# Schematic_nathanlin.net
KiCad netlist of a schematic drawn in Altium Designer
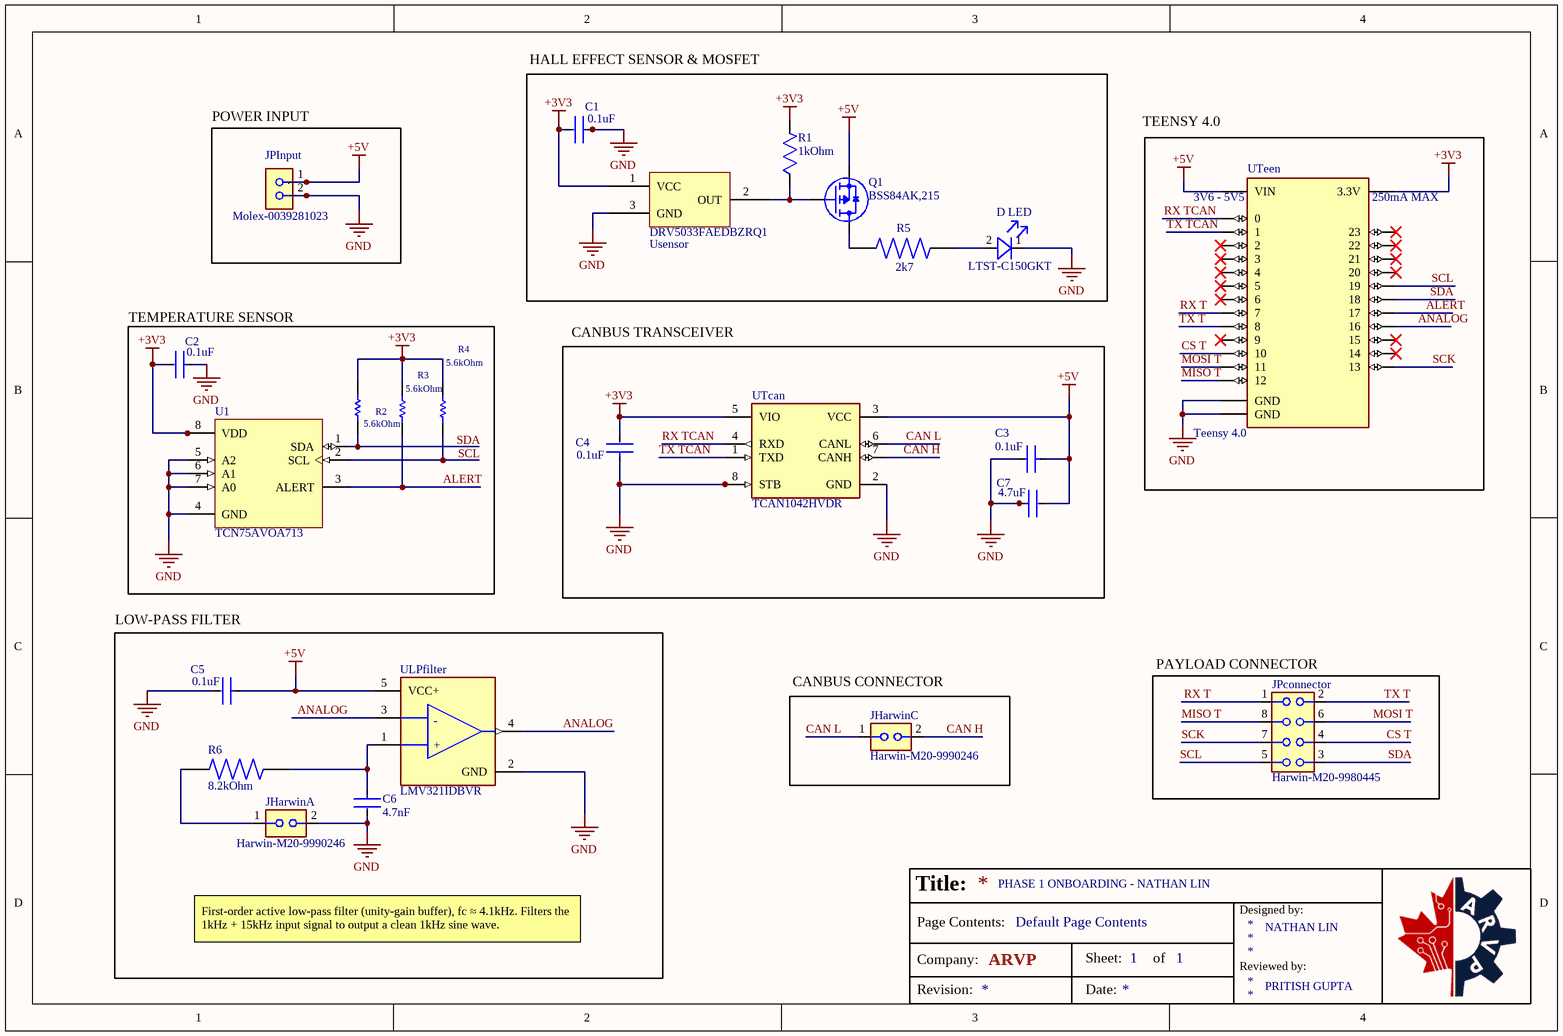
[diagram p0: Schematic_nathanlin.SchDoc]

(export (version "E")
  (design (tool "Eeschema 10.0.6"))
  (components
    (comp (ref "C1")
      (value "0.1uF")
      (footprint "CAP_0603")
      (description "CAP CER 0.1UF 50V X7R 0603")
      (fields (field (name "JLCPCB PART NO.") "C14663"))
      (libsource (lib "Autonomous Robotic Vehicle Project (ARVP)- University of Alberta") (part "CAP_UNPOLARIZED"))
    )
    (comp (ref "C2")
      (value "0.1uF")
      (footprint "CAP_0603")
      (description "CAP CER 0.1UF 50V X7R 0603")
      (fields (field (name "JLCPCB PART NO.") "C14663"))
      (libsource (lib "Autonomous Robotic Vehicle Project (ARVP)- University of Alberta") (part "CAP_UNPOLARIZED"))
    )
    (comp (ref "C3")
      (value "0.1uF")
      (footprint "CAP_0603")
      (description "CAP CER 0.1UF 50V X7R 0603")
      (fields (field (name "JLCPCB PART NO.") "C14663"))
      (libsource (lib "Autonomous Robotic Vehicle Project (ARVP)- University of Alberta") (part "CAP_UNPOLARIZED"))
    )
    (comp (ref "C4")
      (value "0.1uF")
      (footprint "CAP_0603")
      (description "CAP CER 0.1UF 50V X7R 0603")
      (fields (field (name "JLCPCB PART NO.") "C14663"))
      (libsource (lib "Autonomous Robotic Vehicle Project (ARVP)- University of Alberta") (part "CAP_UNPOLARIZED"))
    )
    (comp (ref "C5")
      (value "0.1uF")
      (footprint "CAP_0603")
      (description "CAP CER 0.1UF 50V X7R 0603")
      (fields (field (name "JLCPCB PART NO.") "C14663"))
      (libsource (lib "Autonomous Robotic Vehicle Project (ARVP)- University of Alberta") (part "CAP_UNPOLARIZED"))
    )
    (comp (ref "C6")
      (value "4.7nF")
      (footprint "CAP_0603")
      (description "4700 pF ±10% 50V Ceramic Capacitor X7R 0603 (1608 Metric)")
      (fields (field (name "JLCPCB PART NO.") "C1621"))
      (libsource (lib "Autonomous Robotic Vehicle Project (ARVP)- University of Alberta") (part "CAP_UNPOLARIZED"))
    )
    (comp (ref "C7")
      (value "4.7uF")
      (footprint "CAP_0603")
      (description "CAP CER 4.7UF 16V X5R 0603")
      (fields (field (name "JLCPCB PART NO.") "C19666"))
      (libsource (lib "Autonomous Robotic Vehicle Project (ARVP)- University of Alberta") (part "CAP_UNPOLARIZED"))
    )
    (comp (ref "D LED")
      (value "LTST-C150GKT")
      (footprint "LED_1206")
      (description "LED GREEN CLEAR 1206 SMD")
      (fields (field (name "JLCPCB PART NO.") "C125084"))
      (libsource (lib "Autonomous Robotic Vehicle Project (ARVP)- University of Alberta") (part "LED"))
    )
    (comp (ref "JHarwinA")
      (value "Harwin-M20-9990246")
      (footprint "HARWIN_M20-9990246")
      (description "Connector Header Through Hole 2 position 0.100\" (2.54mm)")
      (fields (field (name "JLCPCB PART NO.") "C3332353"))
      (libsource (lib "Autonomous Robotic Vehicle Project (ARVP)- University of Alberta") (part "M20-9990246"))
    )
    (comp (ref "JHarwinC")
      (value "Harwin-M20-9990246")
      (footprint "HARWIN_M20-9990246")
      (description "Connector Header Through Hole 2 position 0.100\" (2.54mm)")
      (fields (field (name "JLCPCB PART NO.") "C3332353"))
      (libsource (lib "Autonomous Robotic Vehicle Project (ARVP)- University of Alberta") (part "M20-9990246"))
    )
    (comp (ref "JPconnector")
      (value "Harwin-M20-9980445")
      (footprint "HARWIN_M20-9980445")
      (description "Connector Header Through Hole 8 position 0.100\" (2.54mm)")
      (fields (field (name "JLCPCB PART NO.") "C6897587") (field (name "MF") "Harwin Inc."))
      (libsource (lib "Autonomous Robotic Vehicle Project (ARVP)- University of Alberta") (part "M20-9980445"))
    )
    (comp (ref "JPInput")
      (value "Molex-0039281023")
      (footprint "0039281023")
      (description "Connector Header Through Hole 2 position")
      (fields (field (name "JLCPCB PART NO.") "C9900017326"))
      (libsource (lib "Autonomous Robotic Vehicle Project (ARVP)- University of Alberta") (part "0039281023"))
    )
    (comp (ref "Q1")
      (value "BSS84AK,215")
      (footprint "Nexperia_SOT-23-3")
      (description "P-Channel 50 V 180mA (Ta) 350mW (Ta), 1.14W (Tc) Surface Mount TO-236AB")
      (fields (field (name "JLCPCB PART NO.") "C127273"))
      (libsource (lib "Autonomous Robotic Vehicle Project (ARVP)- University of Alberta") (part "BSS84AK,215"))
    )
    (comp (ref "R1")
      (value "1kOhm")
      (footprint "RES_0603")
      (description "1 kOhms ±1% 0.1W, 1/10W Chip Resistor 0603 (1608 Metric) Moisture Resistant Thick Film")
      (fields (field (name "POWER") "100mW") (field (name "TOLERANCE") "1%"))
      (libsource (lib "Autonomous Robotic Vehicle Project (ARVP)- University of Alberta") (part "RES"))
    )
    (comp (ref "R2")
      (value "5.6kOhm")
      (footprint "RESC1608X55X30LL15T15")
      (description "Res Thick Film 0603 5.6K Ohm 5% 1/10W ±200ppm/°C Molded SMD Punched Carrier T/R")
      (libsource (lib "") (part "RES_1"))
    )
    (comp (ref "R3")
      (value "5.6kOhm")
      (footprint "RESC1608X55X30LL15T15")
      (description "Res Thick Film 0603 5.6K Ohm 5% 1/10W ±200ppm/°C Molded SMD Punched Carrier T/R")
      (libsource (lib "") (part "RES_1"))
    )
    (comp (ref "R4")
      (value "5.6kOhm")
      (footprint "RESC1608X55X30LL15T15")
      (description "Res Thick Film 0603 5.6K Ohm 5% 1/10W ±200ppm/°C Molded SMD Punched Carrier T/R")
      (libsource (lib "") (part "RES_1"))
    )
    (comp (ref "R5")
      (value "2k7")
      (footprint "RESC1608X55N")
      (description "2.7 kOhms Â±5% 0.1W, 1/10W Chip Resistor 0603 (1608 Metric) Moisture Resistant Thick Film")
      (fields (field (name "MP") "RC0603JR-072K7L") (field (name "MF") "Yageo"))
      (libsource (lib "Autonomous Robotic Vehicle Project (ARVP)- University of Alberta") (part "RC0603JR-072K7L"))
    )
    (comp (ref "R6")
      (value "8.2kOhm")
      (footprint "RESC2012X60N")
      (description "8.2 kOhms Â±5% 0.125W, 1/8W Chip Resistor 0805 (2012 Metric) Moisture Resistant Thick Film")
      (fields (field (name "MF") "Yageo") (field (name "MP") "RC0805JR-078K2L"))
      (libsource (lib "Autonomous Robotic Vehicle Project (ARVP)- University of Alberta") (part "RC0805JR-078K2L"))
    )
    (comp (ref "U1")
      (value "TCN75AVOA713")
      (footprint "Microchip_SOIC8")
      (description "Temperature Sensor Digital, Local -40°C ~ 125°C 11 b 8-SOIC")
      (fields (field (name "JLCPCB PART NO.") "C144313"))
      (libsource (lib "Autonomous Robotic Vehicle Project (ARVP)- University of Alberta") (part "TCN75AVOA713"))
    )
    (comp (ref "ULPfilter")
      (value "LMV321IDBVR")
      (footprint "SOT95P280X145-5N")
      (description "General Purpose Amplifier 1 Circuit Rail-to-Rail SOT-23-5")
      (fields (field (name "JLCPCB PART NO.") "C7972"))
      (libsource (lib "Autonomous Robotic Vehicle Project (ARVP)- University of Alberta") (part "LMV321IDBVR"))
    )
    (comp (ref "Usensor")
      (value "DRV5033FAEDBZRQ1")
      (footprint "TI_SOT-23-3")
      (description "Digital Switch Omnipolar Switch Open Drain Hall Effect SOT-23-3")
      (fields (field (name "JLCPCB PART NO.") "C2655029"))
      (libsource (lib "Autonomous Robotic Vehicle Project (ARVP)- University of Alberta") (part "DRV5033FAEDBZRQ1"))
    )
    (comp (ref "UTcan")
      (value "TCAN1042HVDR")
      (footprint "TI_SOIC8")
      (description "1/1 Transceiver CANbus 8-SOIC")
      (fields (field (name "JLCPCB PART NO.") "C127869"))
      (libsource (lib "Autonomous Robotic Vehicle Project (ARVP)- University of Alberta") (part "TCAN1042HVDR"))
    )
    (comp (ref "UTeen")
      (value "Teensy 4.0")
      (footprint "TEENSY4.0")
      (description "RT1062 Teensy 4.0 i.MX ARM® Cortex®-M7 MPU Embedded Evaluation Board")
      (libsource (lib "Autonomous Robotic Vehicle Project (ARVP)- University of Alberta") (part "Teensy 4.0"))
    )
  )
  (nets
    (net (code "1") (name "+3V3") (class "Default")
      (node (ref "C1") (pin "2") (pinfunction "2_2") (pintype "passive"))
      (node (ref "C2") (pin "2") (pinfunction "2_2") (pintype "passive"))
      (node (ref "C4") (pin "2") (pinfunction "2_2") (pintype "passive"))
      (node (ref "R1") (pin "2") (pinfunction "2_2") (pintype "passive"))
      (node (ref "R2") (pin "1") (pinfunction "1_1") (pintype "passive"))
      (node (ref "R3") (pin "1") (pinfunction "1_1") (pintype "passive"))
      (node (ref "R4") (pin "2") (pinfunction "2_2") (pintype "passive"))
      (node (ref "U1") (pin "8") (pinfunction "VDD_8") (pintype "power_in"))
      (node (ref "UTcan") (pin "5") (pinfunction "VIO_5") (pintype "power_in"))
      (node (ref "UTeen") (pin "3.3V") (pinfunction "3.3V_3.3V") (pintype "power_in"))
      (node (ref "Usensor") (pin "1") (pinfunction "VCC_1") (pintype "power_in"))
    )
    (net (code "2") (name "+5V") (class "Default")
      (node (ref "C3") (pin "1") (pinfunction "1_1") (pintype "passive"))
      (node (ref "C5") (pin "1") (pinfunction "1_1") (pintype "passive"))
      (node (ref "C7") (pin "2") (pinfunction "2_2") (pintype "passive"))
      (node (ref "JPInput") (pin "1") (pinfunction "1_1") (pintype "passive"))
      (node (ref "Q1") (pin "2") (pinfunction "S_2") (pintype "passive"))
      (node (ref "ULPfilter") (pin "5") (pinfunction "VCC+_5") (pintype "power_in"))
      (node (ref "UTcan") (pin "3") (pinfunction "VCC_3") (pintype "power_in"))
      (node (ref "UTeen") (pin "VIN") (pinfunction "VIN_VIN") (pintype "power_in"))
    )
    (net (code "4") (name "/ALERT") (class "Default")
      (node (ref "R3") (pin "2") (pinfunction "2_2") (pintype "passive"))
      (node (ref "U1") (pin "3") (pinfunction "ALERT_3") (pintype "open_collector"))
      (node (ref "UTeen") (pin "17") (pinfunction "17_17") (pintype "bidirectional"))
    )
    (net (code "5") (name "/ANALOG") (class "Default")
      (node (ref "ULPfilter") (pin "3") (pinfunction "1IN-_3") (pintype "passive"))
      (node (ref "ULPfilter") (pin "4") (pinfunction "OUT_4") (pintype "output"))
      (node (ref "UTeen") (pin "16") (pinfunction "16_16") (pintype "bidirectional"))
    )
    (net (code "6") (name "/CAN H") (class "Default")
      (node (ref "JHarwinC") (pin "2") (pinfunction "2_2") (pintype "passive"))
      (node (ref "UTcan") (pin "7") (pinfunction "CANH_7") (pintype "bidirectional"))
    )
    (net (code "7") (name "/CAN L") (class "Default")
      (node (ref "JHarwinC") (pin "1") (pinfunction "1_1") (pintype "passive"))
      (node (ref "UTcan") (pin "6") (pinfunction "CANL_6") (pintype "bidirectional"))
    )
    (net (code "8") (name "/CS T") (class "Default")
      (node (ref "JPconnector") (pin "4") (pinfunction "4_4") (pintype "passive"))
      (node (ref "UTeen") (pin "10") (pinfunction "10_10") (pintype "bidirectional"))
    )
    (net (code "9") (name "/MISO T") (class "Default")
      (node (ref "JPconnector") (pin "8") (pinfunction "8_8") (pintype "passive"))
      (node (ref "UTeen") (pin "12") (pinfunction "12_12") (pintype "bidirectional"))
    )
    (net (code "10") (name "/MOSI T") (class "Default")
      (node (ref "JPconnector") (pin "6") (pinfunction "6_6") (pintype "passive"))
      (node (ref "UTeen") (pin "11") (pinfunction "11_11") (pintype "bidirectional"))
    )
    (net (code "11") (name "/RX T") (class "Default")
      (node (ref "JPconnector") (pin "1") (pinfunction "1_1") (pintype "passive"))
      (node (ref "UTeen") (pin "7") (pinfunction "7_7") (pintype "bidirectional"))
    )
    (net (code "12") (name "/RX TCAN") (class "Default")
      (node (ref "UTcan") (pin "4") (pinfunction "RXD_4") (pintype "output"))
      (node (ref "UTeen") (pin "0") (pinfunction "0_0") (pintype "bidirectional"))
    )
    (net (code "13") (name "/SCK") (class "Default")
      (node (ref "JPconnector") (pin "7") (pinfunction "7_7") (pintype "passive"))
      (node (ref "UTeen") (pin "13") (pinfunction "13_13") (pintype "bidirectional"))
    )
    (net (code "14") (name "/SCL") (class "Default")
      (node (ref "JPconnector") (pin "5") (pinfunction "5_5") (pintype "passive"))
      (node (ref "UTeen") (pin "19") (pinfunction "19_19") (pintype "bidirectional"))
    )
    (net (code "15") (name "/SDA") (class "Default")
      (node (ref "JPconnector") (pin "3") (pinfunction "3_3") (pintype "passive"))
      (node (ref "UTeen") (pin "18") (pinfunction "18_18") (pintype "bidirectional"))
    )
    (net (code "16") (name "/TX T") (class "Default")
      (node (ref "JPconnector") (pin "2") (pinfunction "2_2") (pintype "passive"))
      (node (ref "UTeen") (pin "8") (pinfunction "8_8") (pintype "bidirectional"))
    )
    (net (code "17") (name "/TX TCAN") (class "Default")
      (node (ref "UTcan") (pin "1") (pinfunction "TXD_1") (pintype "input"))
      (node (ref "UTeen") (pin "1") (pinfunction "1_1") (pintype "bidirectional"))
    )
    (net (code "18") (name "GND") (class "Default")
      (node (ref "C1") (pin "1") (pinfunction "1_1") (pintype "passive"))
      (node (ref "C2") (pin "1") (pinfunction "1_1") (pintype "passive"))
      (node (ref "C3") (pin "2") (pinfunction "2_2") (pintype "passive"))
      (node (ref "C4") (pin "1") (pinfunction "1_1") (pintype "passive"))
      (node (ref "C5") (pin "2") (pinfunction "2_2") (pintype "passive"))
      (node (ref "C6") (pin "2") (pinfunction "2_2") (pintype "passive"))
      (node (ref "C7") (pin "1") (pinfunction "1_1") (pintype "passive"))
      (node (ref "D LED") (pin "1") (pinfunction "C_1") (pintype "passive"))
      (node (ref "JHarwinA") (pin "2") (pinfunction "2_2") (pintype "passive"))
      (node (ref "JPInput") (pin "2") (pinfunction "2_2") (pintype "passive"))
      (node (ref "U1") (pin "4") (pinfunction "GND_4") (pintype "power_in"))
      (node (ref "U1") (pin "5") (pinfunction "A2_5") (pintype "input"))
      (node (ref "U1") (pin "6") (pinfunction "A1_6") (pintype "input"))
      (node (ref "U1") (pin "7") (pinfunction "A0_7") (pintype "input"))
      (node (ref "ULPfilter") (pin "2") (pinfunction "GND_2") (pintype "power_in"))
      (node (ref "UTcan") (pin "2") (pinfunction "GND_2") (pintype "power_in"))
      (node (ref "UTcan") (pin "8") (pinfunction "STB_8") (pintype "input"))
      (node (ref "UTeen") (pin "GND1") (pinfunction "GND_GND1") (pintype "passive"))
      (node (ref "UTeen") (pin "GND2") (pinfunction "GND_GND2") (pintype "passive"))
      (node (ref "Usensor") (pin "3") (pinfunction "GND_3") (pintype "power_in"))
    )
    (net (code "19") (name "Net-(D LED-A)") (class "Default")
      (node (ref "D LED") (pin "2") (pinfunction "A_2") (pintype "passive"))
      (node (ref "R5") (pin "1") (pinfunction "1_1") (pintype "passive"))
    )
    (net (code "20") (name "Net-(JHarwinA-Pad1)") (class "Default")
      (node (ref "JHarwinA") (pin "1") (pinfunction "1_1") (pintype "passive"))
      (node (ref "R6") (pin "1") (pinfunction "1_1") (pintype "passive"))
    )
    (net (code "21") (name "Net-(Q1-D)") (class "Default")
      (node (ref "Q1") (pin "3") (pinfunction "D_3") (pintype "passive"))
      (node (ref "R5") (pin "2") (pinfunction "2_2") (pintype "passive"))
    )
    (net (code "22") (name "Net-(Q1-G)") (class "Default")
      (node (ref "Q1") (pin "1") (pinfunction "G_1") (pintype "passive"))
      (node (ref "R1") (pin "1") (pinfunction "1_1") (pintype "passive"))
      (node (ref "Usensor") (pin "2") (pinfunction "OUT_2") (pintype "open_collector"))
    )
    (net (code "23") (name "Net-(U1-SCL)") (class "Default")
      (node (ref "R4") (pin "1") (pinfunction "1_1") (pintype "passive"))
      (node (ref "U1") (pin "2") (pinfunction "SCL_2") (pintype "input"))
    )
    (net (code "24") (name "Net-(U1-SDA)") (class "Default")
      (node (ref "R2") (pin "2") (pinfunction "2_2") (pintype "passive"))
      (node (ref "U1") (pin "1") (pinfunction "SDA_1") (pintype "bidirectional"))
    )
    (net (code "25") (name "Net-(ULPfilter-1IN+)") (class "Default")
      (node (ref "C6") (pin "1") (pinfunction "1_1") (pintype "passive"))
      (node (ref "R6") (pin "2") (pinfunction "2_2") (pintype "passive"))
      (node (ref "ULPfilter") (pin "1") (pinfunction "1IN+_1") (pintype "passive"))
    )
    (net (code "26") (name "unconnected-(UTeen-Pad2)") (class "Default")
      (node (ref "UTeen") (pin "2") (pinfunction "2_2") (pintype "bidirectional+no_connect"))
    )
    (net (code "27") (name "unconnected-(UTeen-Pad3)") (class "Default")
      (node (ref "UTeen") (pin "3") (pinfunction "3_3") (pintype "bidirectional+no_connect"))
    )
    (net (code "28") (name "unconnected-(UTeen-Pad4)") (class "Default")
      (node (ref "UTeen") (pin "4") (pinfunction "4_4") (pintype "bidirectional+no_connect"))
    )
    (net (code "29") (name "unconnected-(UTeen-Pad5)") (class "Default")
      (node (ref "UTeen") (pin "5") (pinfunction "5_5") (pintype "bidirectional+no_connect"))
    )
    (net (code "30") (name "unconnected-(UTeen-Pad6)") (class "Default")
      (node (ref "UTeen") (pin "6") (pinfunction "6_6") (pintype "bidirectional+no_connect"))
    )
    (net (code "31") (name "unconnected-(UTeen-Pad9)") (class "Default")
      (node (ref "UTeen") (pin "9") (pinfunction "9_9") (pintype "bidirectional+no_connect"))
    )
    (net (code "32") (name "unconnected-(UTeen-Pad14)") (class "Default")
      (node (ref "UTeen") (pin "14") (pinfunction "14_14") (pintype "bidirectional+no_connect"))
    )
    (net (code "33") (name "unconnected-(UTeen-Pad15)") (class "Default")
      (node (ref "UTeen") (pin "15") (pinfunction "15_15") (pintype "bidirectional+no_connect"))
    )
    (net (code "34") (name "unconnected-(UTeen-Pad20)") (class "Default")
      (node (ref "UTeen") (pin "20") (pinfunction "20_20") (pintype "bidirectional+no_connect"))
    )
    (net (code "35") (name "unconnected-(UTeen-Pad21)") (class "Default")
      (node (ref "UTeen") (pin "21") (pinfunction "21_21") (pintype "bidirectional+no_connect"))
    )
    (net (code "36") (name "unconnected-(UTeen-Pad22)") (class "Default")
      (node (ref "UTeen") (pin "22") (pinfunction "22_22") (pintype "bidirectional+no_connect"))
    )
    (net (code "37") (name "unconnected-(UTeen-Pad23)") (class "Default")
      (node (ref "UTeen") (pin "23") (pinfunction "23_23") (pintype "bidirectional+no_connect"))
    )
  )
)
